# PCB_CoLAB_Schematic_V2.net
KiCad netlist of a schematic drawn in EAGLE
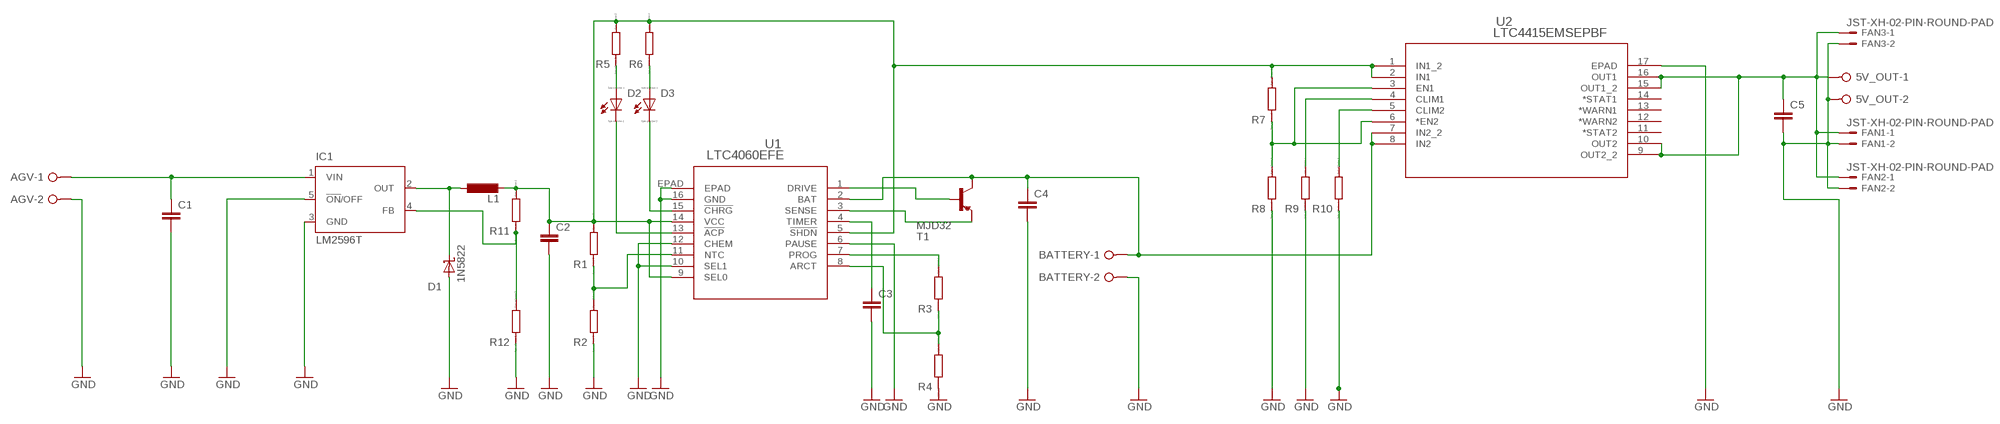
[diagram p0: schematic, sheet 1]

(export (version "E")
  (design (tool "Eeschema 10.0.6"))
  (components
    (comp (ref "5V_OUT")
      (value "W237-02P")
      (footprint "eagle-import:W237-132")
      (libsource (lib "eagle-import") (part "W237-02P"))
    )
    (comp (ref "AGV")
      (value "W237-02P")
      (footprint "eagle-import:W237-132")
      (libsource (lib "eagle-import") (part "W237-02P"))
    )
    (comp (ref "BATTERY")
      (value "W237-02P")
      (footprint "eagle-import:W237-132")
      (libsource (lib "eagle-import") (part "W237-02P"))
    )
    (comp (ref "C1")
      (value "C-EU050-075X075")
      (footprint "eagle-import:C050-075X075")
      (libsource (lib "eagle-import") (part "C-EU050-075X075"))
    )
    (comp (ref "C2")
      (value "C-EU025-050X050")
      (footprint "eagle-import:C025-050X050")
      (libsource (lib "eagle-import") (part "C-EU025-050X050"))
    )
    (comp (ref "C3")
      (value "C-EU025-024X044")
      (footprint "eagle-import:C025-024X044")
      (libsource (lib "eagle-import") (part "C-EU025-024X044"))
    )
    (comp (ref "C4")
      (value "C-EU050-050X075")
      (footprint "eagle-import:C050-050X075")
      (libsource (lib "eagle-import") (part "C-EU050-050X075"))
    )
    (comp (ref "C5")
      (value "C-EU025-024X044")
      (footprint "eagle-import:C025-024X044")
      (libsource (lib "eagle-import") (part "C-EU025-024X044"))
    )
    (comp (ref "D1")
      (value "1N5822")
      (footprint "eagle-import:DIOAD2120W130L950D530P")
      (fields (field (name "MF") "ON Semiconductor"))
      (libsource (lib "eagle-import") (part "1N5822"))
    )
    (comp (ref "D2")
      (value "LED_ELD260")
      (footprint "eagle-import:LED_LD260")
      (libsource (lib "eagle-import") (part "LED_ELD260"))
    )
    (comp (ref "D3")
      (value "LED_ELD260")
      (footprint "eagle-import:LED_LD260")
      (libsource (lib "eagle-import") (part "LED_ELD260"))
    )
    (comp (ref "FAN1")
      (value "JST-XH-02-PIN-ROUND-PAD")
      (footprint "eagle-import:JST-XH-02-PACKAGE-ROUND-PAD")
      (libsource (lib "eagle-import") (part "JST-XH-02-PIN-ROUND-PAD"))
    )
    (comp (ref "FAN2")
      (value "JST-XH-02-PIN-ROUND-PAD")
      (footprint "eagle-import:JST-XH-02-PACKAGE-ROUND-PAD")
      (libsource (lib "eagle-import") (part "JST-XH-02-PIN-ROUND-PAD"))
    )
    (comp (ref "FAN3")
      (value "JST-XH-02-PIN-ROUND-PAD")
      (footprint "eagle-import:JST-XH-02-PACKAGE-ROUND-PAD")
      (libsource (lib "eagle-import") (part "JST-XH-02-PIN-ROUND-PAD"))
    )
    (comp (ref "IC1")
      (value "LM2596T")
      (footprint "eagle-import:T05D")
      (fields (field (name "MPN") "LM2596T-ADJ/LF02"))
      (libsource (lib "eagle-import") (part "LM2596T"))
    )
    (comp (ref "L1")
      (value "L-EU0204/7")
      (footprint "eagle-import:0204_7")
      (libsource (lib "eagle-import") (part "L-EU0204/7"))
    )
    (comp (ref "R1")
      (value "R0204/7")
      (footprint "eagle-import:0204_7")
      (libsource (lib "eagle-import") (part "R0204/7"))
    )
    (comp (ref "R2")
      (value "R0204/7")
      (footprint "eagle-import:0204_7")
      (libsource (lib "eagle-import") (part "R0204/7"))
    )
    (comp (ref "R3")
      (value "R0204/7")
      (footprint "eagle-import:0204_7")
      (libsource (lib "eagle-import") (part "R0204/7"))
    )
    (comp (ref "R4")
      (value "R0204/7")
      (footprint "eagle-import:0204_7")
      (libsource (lib "eagle-import") (part "R0204/7"))
    )
    (comp (ref "R5")
      (value "R0204/7")
      (footprint "eagle-import:0204_7")
      (libsource (lib "eagle-import") (part "R0204/7"))
    )
    (comp (ref "R6")
      (value "R0204/7")
      (footprint "eagle-import:0204_7")
      (libsource (lib "eagle-import") (part "R0204/7"))
    )
    (comp (ref "R7")
      (value "R0204/7")
      (footprint "eagle-import:0204_7")
      (libsource (lib "eagle-import") (part "R0204/7"))
    )
    (comp (ref "R8")
      (value "R0204/7")
      (footprint "eagle-import:0204_7")
      (libsource (lib "eagle-import") (part "R0204/7"))
    )
    (comp (ref "R9")
      (value "R0204/7")
      (footprint "eagle-import:0204_7")
      (libsource (lib "eagle-import") (part "R0204/7"))
    )
    (comp (ref "R10")
      (value "R0204/7")
      (footprint "eagle-import:0204_7")
      (libsource (lib "eagle-import") (part "R0204/7"))
    )
    (comp (ref "R11")
      (value "R0204/7")
      (footprint "eagle-import:0204_7")
      (libsource (lib "eagle-import") (part "R0204/7"))
    )
    (comp (ref "R12")
      (value "R0204/7")
      (footprint "eagle-import:0204_7")
      (libsource (lib "eagle-import") (part "R0204/7"))
    )
    (comp (ref "T1")
      (value "MJD32")
      (footprint "eagle-import:DPAK")
      (libsource (lib "eagle-import") (part "MJD32"))
    )
    (comp (ref "U1")
      (value "LTC4060EFE")
      (footprint "eagle-import:TSSOP-16_FE_BC_LIT")
      (libsource (lib "eagle-import") (part "LTC4060EFE"))
    )
    (comp (ref "U2")
      (value "LTC4415EMSEPBF")
      (footprint "eagle-import:MSOP-16_MSE")
      (fields (field (name "MF") "Analog Devices") (field (name "MP") "LTC4415EMSE#PBF"))
      (libsource (lib "eagle-import") (part "LTC4415EMSEPBF"))
    )
  )
  (nets
    (net (code "1") (name "GND") (class "Default")
      (node (ref "5V_OUT") (pin "2") (pinfunction "KL_2") (pintype "passive"))
      (node (ref "AGV") (pin "2") (pinfunction "KL_2") (pintype "passive"))
      (node (ref "BATTERY") (pin "2") (pinfunction "KL_2") (pintype "passive"))
      (node (ref "C1") (pin "2") (pinfunction "2_2") (pintype "passive"))
      (node (ref "C2") (pin "2") (pinfunction "2_2") (pintype "passive"))
      (node (ref "C3") (pin "2") (pinfunction "2_2") (pintype "passive"))
      (node (ref "C4") (pin "2") (pinfunction "2_2") (pintype "passive"))
      (node (ref "C5") (pin "2") (pinfunction "2_2") (pintype "passive"))
      (node (ref "D1") (pin "A") (pinfunction "A_A") (pintype "passive"))
      (node (ref "FAN1") (pin "2") (pinfunction "S_2") (pintype "passive"))
      (node (ref "FAN2") (pin "2") (pinfunction "S_2") (pintype "passive"))
      (node (ref "FAN3") (pin "2") (pinfunction "S_2") (pintype "passive"))
      (node (ref "IC1") (pin "3") (pinfunction "GND_3") (pintype "power_in"))
      (node (ref "IC1") (pin "5") (pinfunction "~{ON}/OFF_5") (pintype "input"))
      (node (ref "R10") (pin "1") (pinfunction "1_1") (pintype "passive"))
      (node (ref "R12") (pin "1") (pinfunction "1_1") (pintype "passive"))
      (node (ref "R2") (pin "1") (pinfunction "1_1") (pintype "passive"))
      (node (ref "R4") (pin "1") (pinfunction "1_1") (pintype "passive"))
      (node (ref "R8") (pin "1") (pinfunction "1_1") (pintype "passive"))
      (node (ref "R9") (pin "1") (pinfunction "1_1") (pintype "passive"))
      (node (ref "U1") (pin "10") (pinfunction "SEL1_10") (pintype "input"))
      (node (ref "U1") (pin "12") (pinfunction "CHEM_12") (pintype "input"))
      (node (ref "U1") (pin "16") (pinfunction "GND_16") (pintype "power_in"))
      (node (ref "U1") (pin "6") (pinfunction "PAUSE_6") (pintype "input"))
      (node (ref "U1") (pin "EPAD") (pinfunction "EPAD_EPAD") (pintype "passive"))
      (node (ref "U2") (pin "17") (pinfunction "EPAD_17") (pintype "passive"))
    )
    (net (code "2") (name "Net-(5V_OUTA-KL)") (class "Default")
      (node (ref "5V_OUT") (pin "1") (pinfunction "KL_1") (pintype "passive"))
      (node (ref "C5") (pin "1") (pinfunction "1_1") (pintype "passive"))
      (node (ref "FAN1") (pin "1") (pinfunction "S_1") (pintype "passive"))
      (node (ref "FAN2") (pin "1") (pinfunction "S_1") (pintype "passive"))
      (node (ref "FAN3") (pin "1") (pinfunction "S_1") (pintype "passive"))
      (node (ref "U2") (pin "10") (pinfunction "OUT2_10") (pintype "output"))
      (node (ref "U2") (pin "15") (pinfunction "OUT1_2_15") (pintype "output"))
      (node (ref "U2") (pin "16") (pinfunction "OUT1_16") (pintype "output"))
      (node (ref "U2") (pin "9") (pinfunction "OUT2_2_9") (pintype "output"))
    )
    (net (code "3") (name "Net-(AGVA-KL)") (class "Default")
      (node (ref "AGV") (pin "1") (pinfunction "KL_1") (pintype "passive"))
      (node (ref "C1") (pin "1") (pinfunction "1_1") (pintype "passive"))
      (node (ref "IC1") (pin "1") (pinfunction "VIN_1") (pintype "input"))
    )
    (net (code "4") (name "Net-(BATTERYA-KL)") (class "Default")
      (node (ref "BATTERY") (pin "1") (pinfunction "KL_1") (pintype "passive"))
      (node (ref "C4") (pin "1") (pinfunction "1_1") (pintype "passive"))
      (node (ref "T1") (pin "4") (pinfunction "C_4") (pintype "passive"))
      (node (ref "U1") (pin "2") (pinfunction "BAT_2") (pintype "input"))
      (node (ref "U2") (pin "7") (pinfunction "IN2_2_7") (pintype "input"))
      (node (ref "U2") (pin "8") (pinfunction "IN2_8") (pintype "input"))
    )
    (net (code "5") (name "Net-(D2-C)") (class "Default")
      (node (ref "D2") (pin "K") (pinfunction "C_K") (pintype "passive"))
      (node (ref "U1") (pin "13") (pinfunction "~{ACP}_13") (pintype "output"))
    )
    (net (code "6") (name "Net-(D2-PadA)") (class "Default")
      (node (ref "D2") (pin "A") (pinfunction "A_A") (pintype "passive"))
      (node (ref "R5") (pin "1") (pinfunction "1_1") (pintype "passive"))
    )
    (net (code "7") (name "Net-(D3-C)") (class "Default")
      (node (ref "D3") (pin "K") (pinfunction "C_K") (pintype "passive"))
      (node (ref "U1") (pin "15") (pinfunction "~{CHRG}_15") (pintype "output"))
    )
    (net (code "8") (name "Net-(D3-PadA)") (class "Default")
      (node (ref "D3") (pin "A") (pinfunction "A_A") (pintype "passive"))
      (node (ref "R6") (pin "1") (pinfunction "1_1") (pintype "passive"))
    )
    (net (code "9") (name "Net-(IC1-FB)") (class "Default")
      (node (ref "IC1") (pin "4") (pinfunction "FB_4") (pintype "input"))
      (node (ref "R11") (pin "1") (pinfunction "1_1") (pintype "passive"))
      (node (ref "R12") (pin "2") (pinfunction "2_2") (pintype "passive"))
    )
    (net (code "10") (name "Net-(IC1-OUT)") (class "Default")
      (node (ref "D1") (pin "C") (pinfunction "C_C") (pintype "passive"))
      (node (ref "IC1") (pin "2") (pinfunction "OUT_2") (pintype "output"))
      (node (ref "L1") (pin "1") (pinfunction "1_1") (pintype "passive"))
    )
    (net (code "11") (name "Net-(T1-B)") (class "Default")
      (node (ref "T1") (pin "1") (pinfunction "B_1") (pintype "passive"))
      (node (ref "U1") (pin "1") (pinfunction "DRIVE_1") (pintype "output"))
    )
    (net (code "12") (name "Net-(T1-E)") (class "Default")
      (node (ref "T1") (pin "3") (pinfunction "E_3") (pintype "passive"))
      (node (ref "U1") (pin "3") (pinfunction "SENSE_3") (pintype "input"))
    )
    (net (code "13") (name "Net-(U1-ARCT)") (class "Default")
      (node (ref "R3") (pin "1") (pinfunction "1_1") (pintype "passive"))
      (node (ref "R4") (pin "2") (pinfunction "2_2") (pintype "passive"))
      (node (ref "U1") (pin "8") (pinfunction "ARCT_8") (pintype "input"))
    )
    (net (code "14") (name "Net-(U1-NTC)") (class "Default")
      (node (ref "R1") (pin "1") (pinfunction "1_1") (pintype "passive"))
      (node (ref "R2") (pin "2") (pinfunction "2_2") (pintype "passive"))
      (node (ref "U1") (pin "11") (pinfunction "NTC_11") (pintype "input"))
    )
    (net (code "15") (name "Net-(U1-PROG)") (class "Default")
      (node (ref "R3") (pin "2") (pinfunction "2_2") (pintype "passive"))
      (node (ref "U1") (pin "7") (pinfunction "PROG_7") (pintype "input"))
    )
    (net (code "16") (name "Net-(U1-SEL0)") (class "Default")
      (node (ref "C2") (pin "1") (pinfunction "1_1") (pintype "passive"))
      (node (ref "L1") (pin "2") (pinfunction "2_2") (pintype "passive"))
      (node (ref "R1") (pin "2") (pinfunction "2_2") (pintype "passive"))
      (node (ref "R11") (pin "2") (pinfunction "2_2") (pintype "passive"))
      (node (ref "R5") (pin "2") (pinfunction "2_2") (pintype "passive"))
      (node (ref "R6") (pin "2") (pinfunction "2_2") (pintype "passive"))
      (node (ref "R7") (pin "2") (pinfunction "2_2") (pintype "passive"))
      (node (ref "U1") (pin "14") (pinfunction "VCC_14") (pintype "power_in"))
      (node (ref "U1") (pin "5") (pinfunction "~{SHDN}_5") (pintype "input"))
      (node (ref "U1") (pin "9") (pinfunction "SEL0_9") (pintype "input"))
      (node (ref "U2") (pin "1") (pinfunction "IN1_2_1") (pintype "input"))
      (node (ref "U2") (pin "2") (pinfunction "IN1_2") (pintype "input"))
    )
    (net (code "17") (name "Net-(U1-TIMER)") (class "Default")
      (node (ref "C3") (pin "1") (pinfunction "1_1") (pintype "passive"))
      (node (ref "U1") (pin "4") (pinfunction "TIMER_4") (pintype "input"))
    )
    (net (code "18") (name "Net-(U2-*EN2)") (class "Default")
      (node (ref "R7") (pin "1") (pinfunction "1_1") (pintype "passive"))
      (node (ref "R8") (pin "2") (pinfunction "2_2") (pintype "passive"))
      (node (ref "U2") (pin "3") (pinfunction "EN1_3") (pintype "input"))
      (node (ref "U2") (pin "6") (pinfunction "*EN2_6") (pintype "input"))
    )
    (net (code "19") (name "Net-(U2-CLIM1)") (class "Default")
      (node (ref "R9") (pin "2") (pinfunction "2_2") (pintype "passive"))
      (node (ref "U2") (pin "4") (pinfunction "CLIM1_4") (pintype "passive"))
    )
    (net (code "20") (name "Net-(U2-CLIM2)") (class "Default")
      (node (ref "R10") (pin "2") (pinfunction "2_2") (pintype "passive"))
      (node (ref "U2") (pin "5") (pinfunction "CLIM2_5") (pintype "passive"))
    )
    (net (code "21") (name "unconnected-(U2-*STAT1-Pad14)") (class "Default")
      (node (ref "U2") (pin "14") (pinfunction "*STAT1_14") (pintype "output"))
    )
    (net (code "22") (name "unconnected-(U2-*STAT2-Pad11)") (class "Default")
      (node (ref "U2") (pin "11") (pinfunction "*STAT2_11") (pintype "output"))
    )
    (net (code "23") (name "unconnected-(U2-*WARN1-Pad13)") (class "Default")
      (node (ref "U2") (pin "13") (pinfunction "*WARN1_13") (pintype "output"))
    )
    (net (code "24") (name "unconnected-(U2-*WARN2-Pad12)") (class "Default")
      (node (ref "U2") (pin "12") (pinfunction "*WARN2_12") (pintype "output"))
    )
  )
)
